# wumpus.net
KiCad netlist of a schematic drawn in EasyEDA
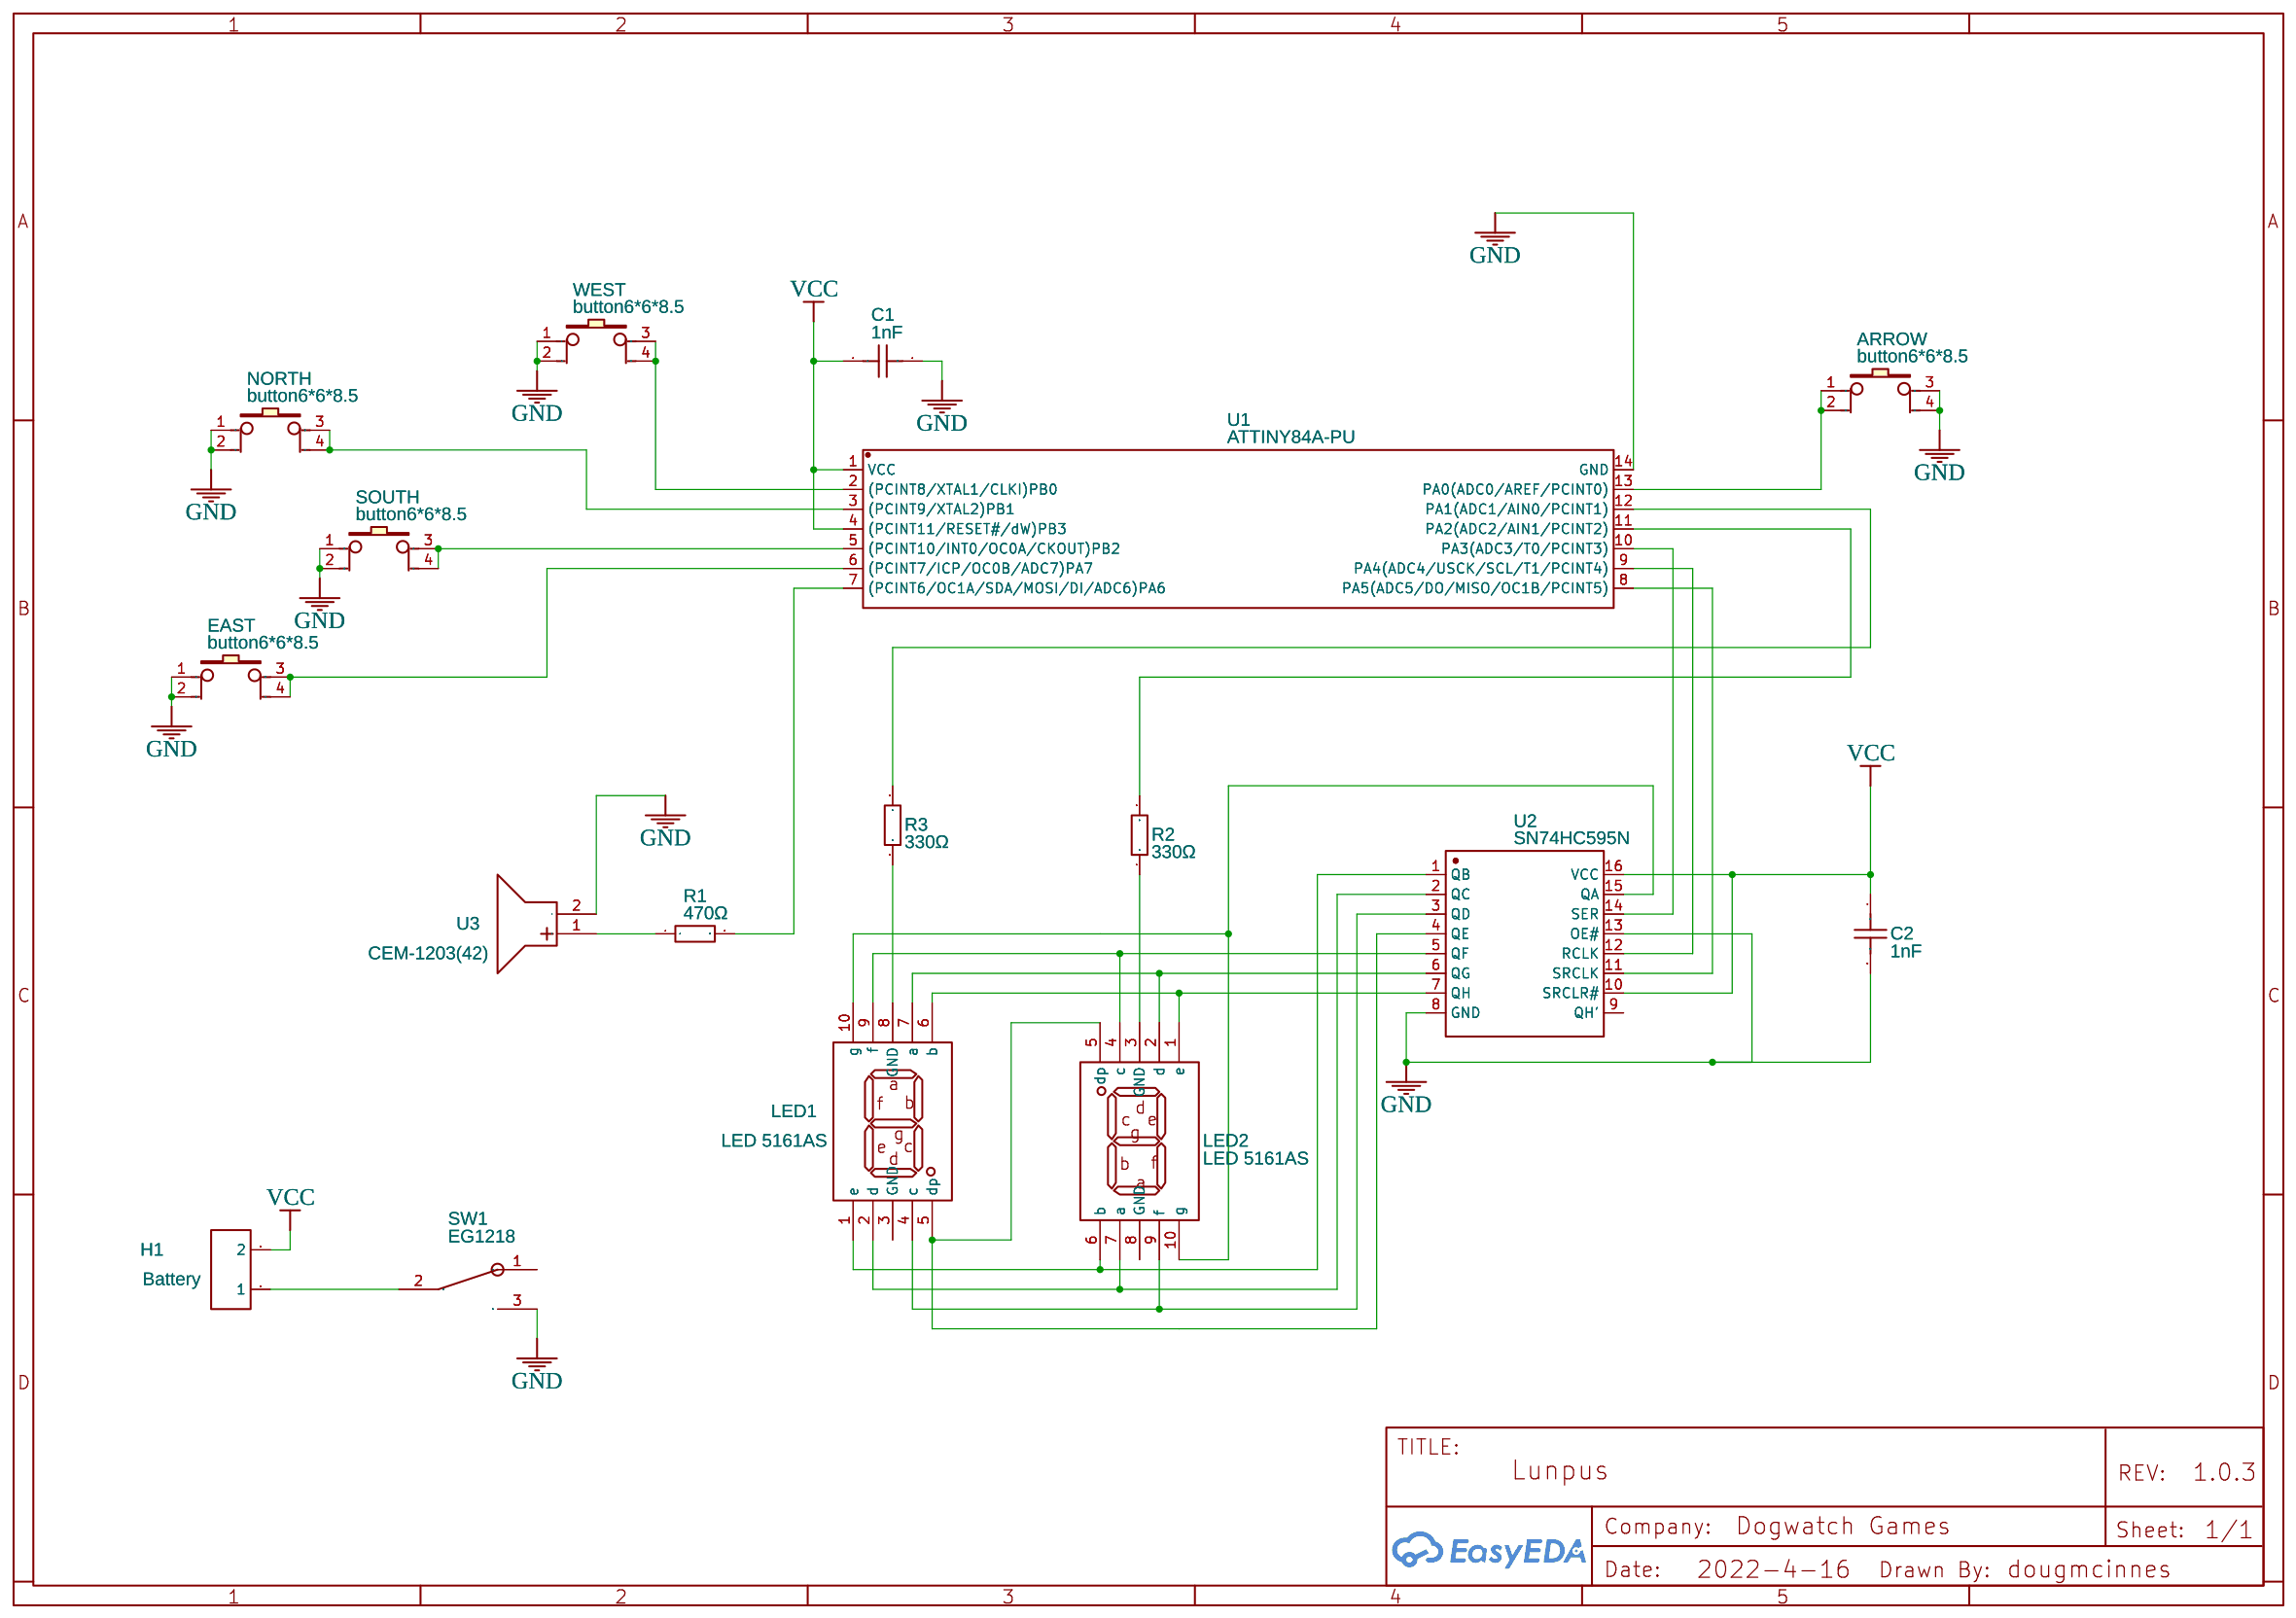
[diagram p0: schematic sheet]

(export (version "E")
  (design (tool "Eeschema 10.0.6"))
  (components
    (comp (ref "ARROW")
      (value "button6*6*8.5")
      (fields (field (name "BOM_Supplier Part") "C59980"))
      (libsource (lib "") (part "button6*6*8.5_3"))
    )
    (comp (ref "C1")
      (value "1nF")
      (fields
        (field (name "BOM_Manufacturer Part") "CC1H102MA1PDB44B3003")
        (field (name "BOM_Supplier Part") "C353905")
      )
      (libsource (lib "") (part "CC1H102MA1PDB44B3003_1"))
    )
    (comp (ref "C2")
      (value "1nF")
      (fields
        (field (name "BOM_Manufacturer Part") "CC1H102MA1PDB44B3003")
        (field (name "BOM_Supplier Part") "C353905")
      )
      (libsource (lib "") (part "CC1H102MA1PDB44B3003"))
    )
    (comp (ref "EAST")
      (value "button6*6*8.5")
      (fields (field (name "BOM_Supplier Part") "C59980"))
      (libsource (lib "") (part "button6*6*8.5_2"))
    )
    (comp (ref "H1")
      (value "Battery")
      (fields (field (name "BOM_Manufacturer Part") "826629-2") (field (name "BOM_Supplier Part") "C86471"))
      (libsource (lib "") (part "Header-Male-2.54_1x2"))
    )
    (comp (ref "LED1")
      (value "LED 5161AS")
      (fields (field (name "BOM_Manufacturer Part") "FJ3191AH") (field (name "BOM_Supplier Part") "C44296"))
      (libsource (lib "") (part "LED 5161AS"))
    )
    (comp (ref "LED2")
      (value "LED 5161AS")
      (fields (field (name "BOM_Manufacturer Part") "FJ3191AH") (field (name "BOM_Supplier Part") "C44296"))
      (libsource (lib "") (part "LED 5161AS_1"))
    )
    (comp (ref "NORTH")
      (value "button6*6*8.5")
      (fields (field (name "BOM_Supplier Part") "C59980"))
      (libsource (lib "") (part "button6*6*8.5"))
    )
    (comp (ref "R1")
      (value "470Ω")
      (fields
        (field (name "BOM_Manufacturer Part") "MFR0W8F4700A50")
        (field (name "BOM_Supplier Part") "C61674")
      )
      (libsource (lib "") (part "470Ω"))
    )
    (comp (ref "R2")
      (value "330Ω")
      (fields
        (field (name "BOM_Manufacturer Part") "MFR0W4F3300A50")
        (field (name "BOM_Supplier Part") "C58608")
      )
      (libsource (lib "") (part "330Ω"))
    )
    (comp (ref "R3")
      (value "330Ω")
      (fields
        (field (name "BOM_Manufacturer Part") "MFR0W4F3300A50")
        (field (name "BOM_Supplier Part") "C58608")
      )
      (libsource (lib "") (part "330Ω"))
    )
    (comp (ref "SOUTH")
      (value "button6*6*8.5")
      (fields (field (name "BOM_Supplier Part") "C59980"))
      (libsource (lib "") (part "button6*6*8.5_1"))
    )
    (comp (ref "SW1")
      (value "EG1218")
      (fields (field (name "BOM_Supplier Part") "C273394"))
      (libsource (lib "") (part "EG1218"))
    )
    (comp (ref "U1")
      (value "ATTINY84A-PU")
      (fields (field (name "BOM_Supplier Part") "C145560"))
      (libsource (lib "") (part "ATTINY84A-PU"))
    )
    (comp (ref "U2")
      (value "SN74HC595N")
      (fields (field (name "BOM_Supplier Part") "C78711"))
      (libsource (lib "") (part "SN74HC595N"))
    )
    (comp (ref "U3")
      (value "CEM-1203(42)")
      (fields (field (name "BOM_Supplier Part") "102-1153-ND"))
      (libsource (lib "") (part "CEM-1203(42)"))
    )
    (comp (ref "WEST")
      (value "button6*6*8.5")
      (fields (field (name "BOM_Supplier Part") "C59980"))
      (libsource (lib "") (part "button6*6*8.5_4"))
    )
  )
  (nets
    (net (code "1") (name "GND") (class "Default")
      (node (ref "ARROW") (pin "3") (pinfunction "3_3") (pintype "input"))
      (node (ref "ARROW") (pin "4") (pinfunction "4_4") (pintype "input"))
      (node (ref "C1") (pin "1") (pinfunction "1_1") (pintype "unspecified"))
      (node (ref "C2") (pin "2") (pinfunction "2_2") (pintype "unspecified"))
      (node (ref "EAST") (pin "1") (pinfunction "1_1") (pintype "input"))
      (node (ref "EAST") (pin "2") (pinfunction "2_2") (pintype "input"))
      (node (ref "NORTH") (pin "1") (pinfunction "1_1") (pintype "input"))
      (node (ref "NORTH") (pin "2") (pinfunction "2_2") (pintype "input"))
      (node (ref "SOUTH") (pin "1") (pinfunction "1_1") (pintype "input"))
      (node (ref "SOUTH") (pin "2") (pinfunction "2_2") (pintype "input"))
      (node (ref "SW1") (pin "3") (pinfunction "3_3") (pintype "input"))
      (node (ref "U1") (pin "14") (pinfunction "GND_14") (pintype "unspecified"))
      (node (ref "U2") (pin "13") (pinfunction "OE#_13") (pintype "unspecified"))
      (node (ref "U2") (pin "8") (pinfunction "GND_8") (pintype "unspecified"))
      (node (ref "U3") (pin "2") (pinfunction "-_2") (pintype "unspecified"))
      (node (ref "WEST") (pin "1") (pinfunction "1_1") (pintype "input"))
      (node (ref "WEST") (pin "2") (pinfunction "2_2") (pintype "input"))
    )
    (net (code "2") (name "Net-(H1-Pad1)") (class "Default")
      (node (ref "H1") (pin "1") (pinfunction "1_1") (pintype "unspecified"))
      (node (ref "SW1") (pin "2") (pinfunction "2_2") (pintype "input"))
    )
    (net (code "3") (name "Net-(LED1-GND-Pad8)") (class "Default")
      (node (ref "LED1") (pin "8") (pinfunction "GND_8") (pintype "input"))
      (node (ref "R3") (pin "1") (pinfunction "1_1") (pintype "input"))
    )
    (net (code "4") (name "Net-(LED1-a)") (class "Default")
      (node (ref "LED1") (pin "7") (pinfunction "a_7") (pintype "input"))
      (node (ref "LED2") (pin "2") (pinfunction "d_2") (pintype "input"))
      (node (ref "U2") (pin "6") (pinfunction "QG_6") (pintype "unspecified"))
    )
    (net (code "5") (name "Net-(LED1-b)") (class "Default")
      (node (ref "LED1") (pin "6") (pinfunction "b_6") (pintype "input"))
      (node (ref "LED2") (pin "1") (pinfunction "e_1") (pintype "input"))
      (node (ref "U2") (pin "7") (pinfunction "QH_7") (pintype "unspecified"))
    )
    (net (code "6") (name "Net-(LED1-c)") (class "Default")
      (node (ref "LED1") (pin "4") (pinfunction "c_4") (pintype "input"))
      (node (ref "LED2") (pin "9") (pinfunction "f_9") (pintype "input"))
      (node (ref "U2") (pin "3") (pinfunction "QD_3") (pintype "unspecified"))
    )
    (net (code "7") (name "Net-(LED1-d)") (class "Default")
      (node (ref "LED1") (pin "2") (pinfunction "d_2") (pintype "input"))
      (node (ref "LED2") (pin "7") (pinfunction "a_7") (pintype "input"))
      (node (ref "U2") (pin "2") (pinfunction "QC_2") (pintype "unspecified"))
    )
    (net (code "8") (name "Net-(LED1-dp)") (class "Default")
      (node (ref "LED1") (pin "5") (pinfunction "dp_5") (pintype "input"))
      (node (ref "LED2") (pin "5") (pinfunction "dp_5") (pintype "input"))
      (node (ref "U2") (pin "4") (pinfunction "QE_4") (pintype "unspecified"))
    )
    (net (code "9") (name "Net-(LED1-e)") (class "Default")
      (node (ref "LED1") (pin "1") (pinfunction "e_1") (pintype "input"))
      (node (ref "LED2") (pin "6") (pinfunction "b_6") (pintype "input"))
      (node (ref "U2") (pin "1") (pinfunction "QB_1") (pintype "unspecified"))
    )
    (net (code "10") (name "Net-(LED1-f)") (class "Default")
      (node (ref "LED1") (pin "9") (pinfunction "f_9") (pintype "input"))
      (node (ref "LED2") (pin "4") (pinfunction "c_4") (pintype "input"))
      (node (ref "U2") (pin "5") (pinfunction "QF_5") (pintype "unspecified"))
    )
    (net (code "11") (name "Net-(LED1-g)") (class "Default")
      (node (ref "LED1") (pin "10") (pinfunction "g_10") (pintype "input"))
      (node (ref "LED2") (pin "10") (pinfunction "g_10") (pintype "input"))
      (node (ref "U2") (pin "15") (pinfunction "QA_15") (pintype "unspecified"))
    )
    (net (code "12") (name "Net-(LED2-GND-Pad3)") (class "Default")
      (node (ref "LED2") (pin "3") (pinfunction "GND_3") (pintype "input"))
      (node (ref "R2") (pin "1") (pinfunction "1_1") (pintype "input"))
    )
    (net (code "13") (name "Net-(U1-(PCINT6{slash}OC1A{slash}SDA{slash}MOSI{slash}DI{slash}ADC6)PA6)") (class "Default")
      (node (ref "R1") (pin "2") (pinfunction "2_2") (pintype "input"))
      (node (ref "U1") (pin "7") (pinfunction "(PCINT6/OC1A/SDA/MOSI/DI/ADC6)PA6_7") (pintype "unspecified"))
    )
    (net (code "14") (name "Net-(U1-(PCINT7{slash}ICP{slash}OC0B{slash}ADC7)PA7)") (class "Default")
      (node (ref "EAST") (pin "3") (pinfunction "3_3") (pintype "input"))
      (node (ref "EAST") (pin "4") (pinfunction "4_4") (pintype "input"))
      (node (ref "U1") (pin "6") (pinfunction "(PCINT7/ICP/OC0B/ADC7)PA7_6") (pintype "unspecified"))
    )
    (net (code "15") (name "Net-(U1-(PCINT8{slash}XTAL1{slash}CLKI)PB0)") (class "Default")
      (node (ref "U1") (pin "2") (pinfunction "(PCINT8/XTAL1/CLKI)PB0_2") (pintype "unspecified"))
      (node (ref "WEST") (pin "3") (pinfunction "3_3") (pintype "input"))
      (node (ref "WEST") (pin "4") (pinfunction "4_4") (pintype "input"))
    )
    (net (code "16") (name "Net-(U1-(PCINT9{slash}XTAL2)PB1)") (class "Default")
      (node (ref "NORTH") (pin "3") (pinfunction "3_3") (pintype "input"))
      (node (ref "NORTH") (pin "4") (pinfunction "4_4") (pintype "input"))
      (node (ref "U1") (pin "3") (pinfunction "(PCINT9/XTAL2)PB1_3") (pintype "unspecified"))
    )
    (net (code "17") (name "Net-(U1-(PCINT10{slash}INT0{slash}OC0A{slash}CKOUT)PB2)") (class "Default")
      (node (ref "SOUTH") (pin "3") (pinfunction "3_3") (pintype "input"))
      (node (ref "SOUTH") (pin "4") (pinfunction "4_4") (pintype "input"))
      (node (ref "U1") (pin "5") (pinfunction "(PCINT10/INT0/OC0A/CKOUT)PB2_5") (pintype "unspecified"))
    )
    (net (code "18") (name "Net-(U1-PA0(ADC0{slash}AREF{slash}PCINT0))") (class "Default")
      (node (ref "ARROW") (pin "1") (pinfunction "1_1") (pintype "input"))
      (node (ref "ARROW") (pin "2") (pinfunction "2_2") (pintype "input"))
      (node (ref "U1") (pin "13") (pinfunction "PA0(ADC0/AREF/PCINT0)_13") (pintype "unspecified"))
    )
    (net (code "19") (name "Net-(U1-PA1(ADC1{slash}AIN0{slash}PCINT1))") (class "Default")
      (node (ref "R3") (pin "2") (pinfunction "2_2") (pintype "input"))
      (node (ref "U1") (pin "12") (pinfunction "PA1(ADC1/AIN0/PCINT1)_12") (pintype "unspecified"))
    )
    (net (code "20") (name "Net-(U1-PA2(ADC2{slash}AIN1{slash}PCINT2))") (class "Default")
      (node (ref "R2") (pin "2") (pinfunction "2_2") (pintype "input"))
      (node (ref "U1") (pin "11") (pinfunction "PA2(ADC2/AIN1/PCINT2)_11") (pintype "unspecified"))
    )
    (net (code "21") (name "Net-(U1-PA3(ADC3{slash}T0{slash}PCINT3))") (class "Default")
      (node (ref "U1") (pin "10") (pinfunction "PA3(ADC3/T0/PCINT3)_10") (pintype "unspecified"))
      (node (ref "U2") (pin "14") (pinfunction "SER_14") (pintype "unspecified"))
    )
    (net (code "22") (name "Net-(U1-PA4(ADC4{slash}USCK{slash}SCL{slash}T1{slash}PCINT4))") (class "Default")
      (node (ref "U1") (pin "9") (pinfunction "PA4(ADC4/USCK/SCL/T1/PCINT4)_9") (pintype "unspecified"))
      (node (ref "U2") (pin "12") (pinfunction "RCLK_12") (pintype "unspecified"))
    )
    (net (code "23") (name "Net-(U1-PA5(ADC5{slash}DO{slash}MISO{slash}OC1B{slash}PCINT5))") (class "Default")
      (node (ref "U1") (pin "8") (pinfunction "PA5(ADC5/DO/MISO/OC1B/PCINT5)_8") (pintype "unspecified"))
      (node (ref "U2") (pin "11") (pinfunction "SRCLK_11") (pintype "unspecified"))
    )
    (net (code "24") (name "Net-(U3-+)") (class "Default")
      (node (ref "R1") (pin "1") (pinfunction "1_1") (pintype "input"))
      (node (ref "U3") (pin "1") (pinfunction "+_1") (pintype "unspecified"))
    )
    (net (code "25") (name "VCC") (class "Default")
      (node (ref "C1") (pin "2") (pinfunction "2_2") (pintype "unspecified"))
      (node (ref "C2") (pin "1") (pinfunction "1_1") (pintype "unspecified"))
      (node (ref "H1") (pin "2") (pinfunction "2_2") (pintype "unspecified"))
      (node (ref "U1") (pin "1") (pinfunction "VCC_1") (pintype "unspecified"))
      (node (ref "U1") (pin "4") (pinfunction "(PCINT11/RESET#/dW)PB3_4") (pintype "unspecified"))
      (node (ref "U2") (pin "10") (pinfunction "SRCLR#_10") (pintype "unspecified"))
      (node (ref "U2") (pin "16") (pinfunction "VCC_16") (pintype "unspecified"))
    )
    (net (code "26") (name "unconnected-(LED1-GND-Pad3)") (class "Default")
      (node (ref "LED1") (pin "3") (pinfunction "GND_3") (pintype "input"))
    )
    (net (code "27") (name "unconnected-(LED2-GND-Pad8)") (class "Default")
      (node (ref "LED2") (pin "8") (pinfunction "GND_8") (pintype "input"))
    )
    (net (code "28") (name "unconnected-(SW1-Pad1)") (class "Default")
      (node (ref "SW1") (pin "1") (pinfunction "1_1") (pintype "input"))
    )
    (net (code "29") (name "unconnected-(U2-QH'-Pad9)") (class "Default")
      (node (ref "U2") (pin "9") (pinfunction "QH'_9") (pintype "unspecified"))
    )
  )
)
